# design.net
KiCad netlist of a schematic drawn in EasyEDA
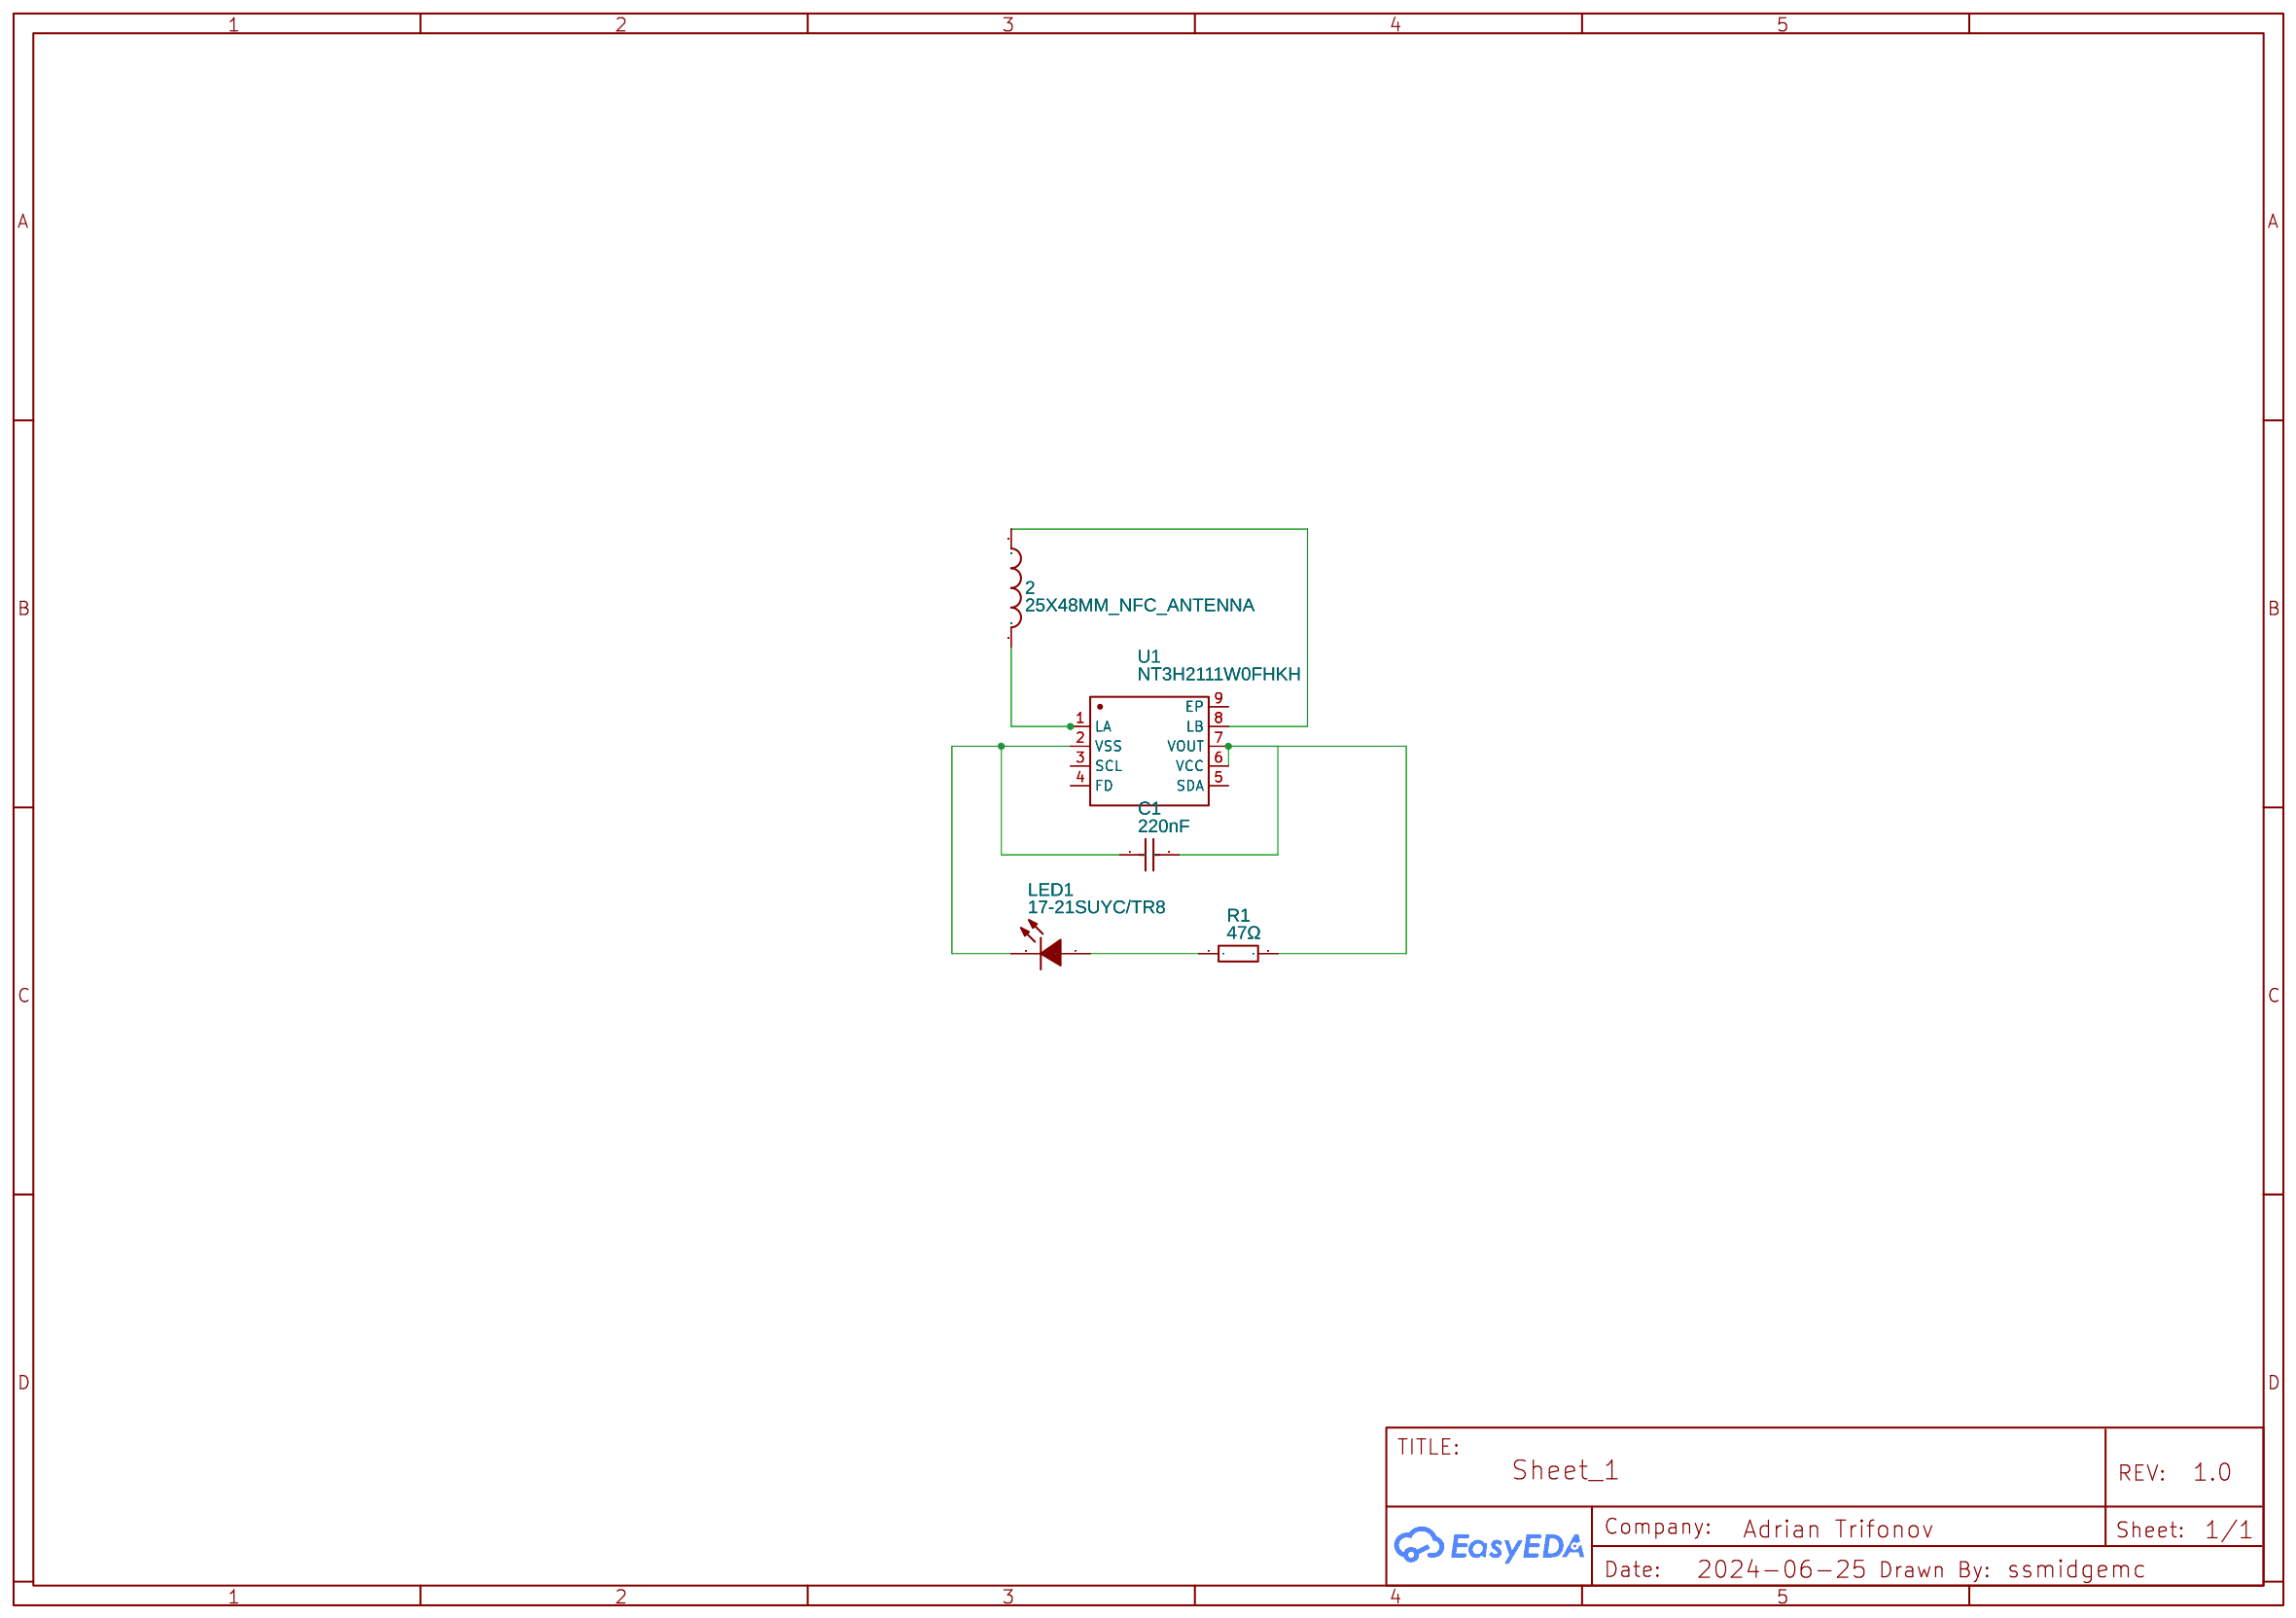
[diagram p0: schematic sheet]

(export (version "E")
  (design (tool "Eeschema 10.0.6"))
  (components
    (comp (ref "2") (value "25X48MM_NFC_ANTENNA") (libsource (lib "") (part "25X48MM_NFC_ANTENNA")))
    (comp (ref "C1")
      (value "220nF")
      (fields
        (field (name "Manufacturer Part") "CL10B224KA8NNNC")
        (field (name "Manufacturer") "SAMSUNG(三星)")
      )
      (libsource (lib "") (part "CL10B224KA8NNNC"))
    )
    (comp (ref "LED1")
      (value "17-21SUYC/TR8")
      (fields (field (name "Manufacturer Part") "KT-0805黄灯") (field (name "Manufacturer") "KENTO"))
      (libsource (lib "") (part "17-21SUYC/TR8"))
    )
    (comp (ref "R1")
      (value "47Ω")
      (fields
        (field (name "Manufacturer Part") "0603WAF470JT5E")
        (field (name "Manufacturer") "UNI-ROYAL(厚声)")
      )
      (libsource (lib "") (part "0603WAF470JT5E"))
    )
    (comp (ref "U1")
      (value "NT3H2111W0FHKH")
      (fields (field (name "Manufacturer") "NXP(恩智浦)"))
      (libsource (lib "") (part "NT3H2111W0FHKH"))
    )
  )
  (nets
    (net (code "1") (name "Net-(LED1-+)") (class "Default")
      (node (ref "LED1") (pin "1") (pinfunction "+_1") (pintype "unspecified"))
      (node (ref "R1") (pin "1") (pinfunction "1_1") (pintype "input"))
    )
    (net (code "2") (name "Net-(LED1--)") (class "Default")
      (node (ref "C1") (pin "1") (pinfunction "1_1") (pintype "input"))
      (node (ref "LED1") (pin "2") (pinfunction "-_2") (pintype "unspecified"))
      (node (ref "U1") (pin "2") (pinfunction "VSS_2") (pintype "unspecified"))
    )
    (net (code "3") (name "Net-(U1-LA)") (class "Default")
      (node (ref "2") (pin "P$2") (pinfunction "P$2_P$2") (pintype "bidirectional"))
      (node (ref "U1") (pin "1") (pinfunction "LA_1") (pintype "unspecified"))
    )
    (net (code "4") (name "Net-(U1-LB)") (class "Default")
      (node (ref "2") (pin "P$1") (pinfunction "P$1_P$1") (pintype "bidirectional"))
      (node (ref "U1") (pin "8") (pinfunction "LB_8") (pintype "unspecified"))
    )
    (net (code "5") (name "Net-(U1-VCC)") (class "Default")
      (node (ref "C1") (pin "2") (pinfunction "2_2") (pintype "input"))
      (node (ref "R1") (pin "2") (pinfunction "2_2") (pintype "input"))
      (node (ref "U1") (pin "6") (pinfunction "VCC_6") (pintype "unspecified"))
      (node (ref "U1") (pin "7") (pinfunction "VOUT_7") (pintype "unspecified"))
    )
    (net (code "6") (name "unconnected-(U1-EP-Pad9)") (class "Default")
      (node (ref "U1") (pin "9") (pinfunction "EP_9") (pintype "unspecified"))
    )
    (net (code "7") (name "unconnected-(U1-FD-Pad4)") (class "Default")
      (node (ref "U1") (pin "4") (pinfunction "FD_4") (pintype "unspecified"))
    )
    (net (code "8") (name "unconnected-(U1-SCL-Pad3)") (class "Default")
      (node (ref "U1") (pin "3") (pinfunction "SCL_3") (pintype "unspecified"))
    )
    (net (code "9") (name "unconnected-(U1-SDA-Pad5)") (class "Default")
      (node (ref "U1") (pin "5") (pinfunction "SDA_5") (pintype "unspecified"))
    )
  )
)
